# RS422.net
KiCad netlist of a schematic drawn in Altium Designer
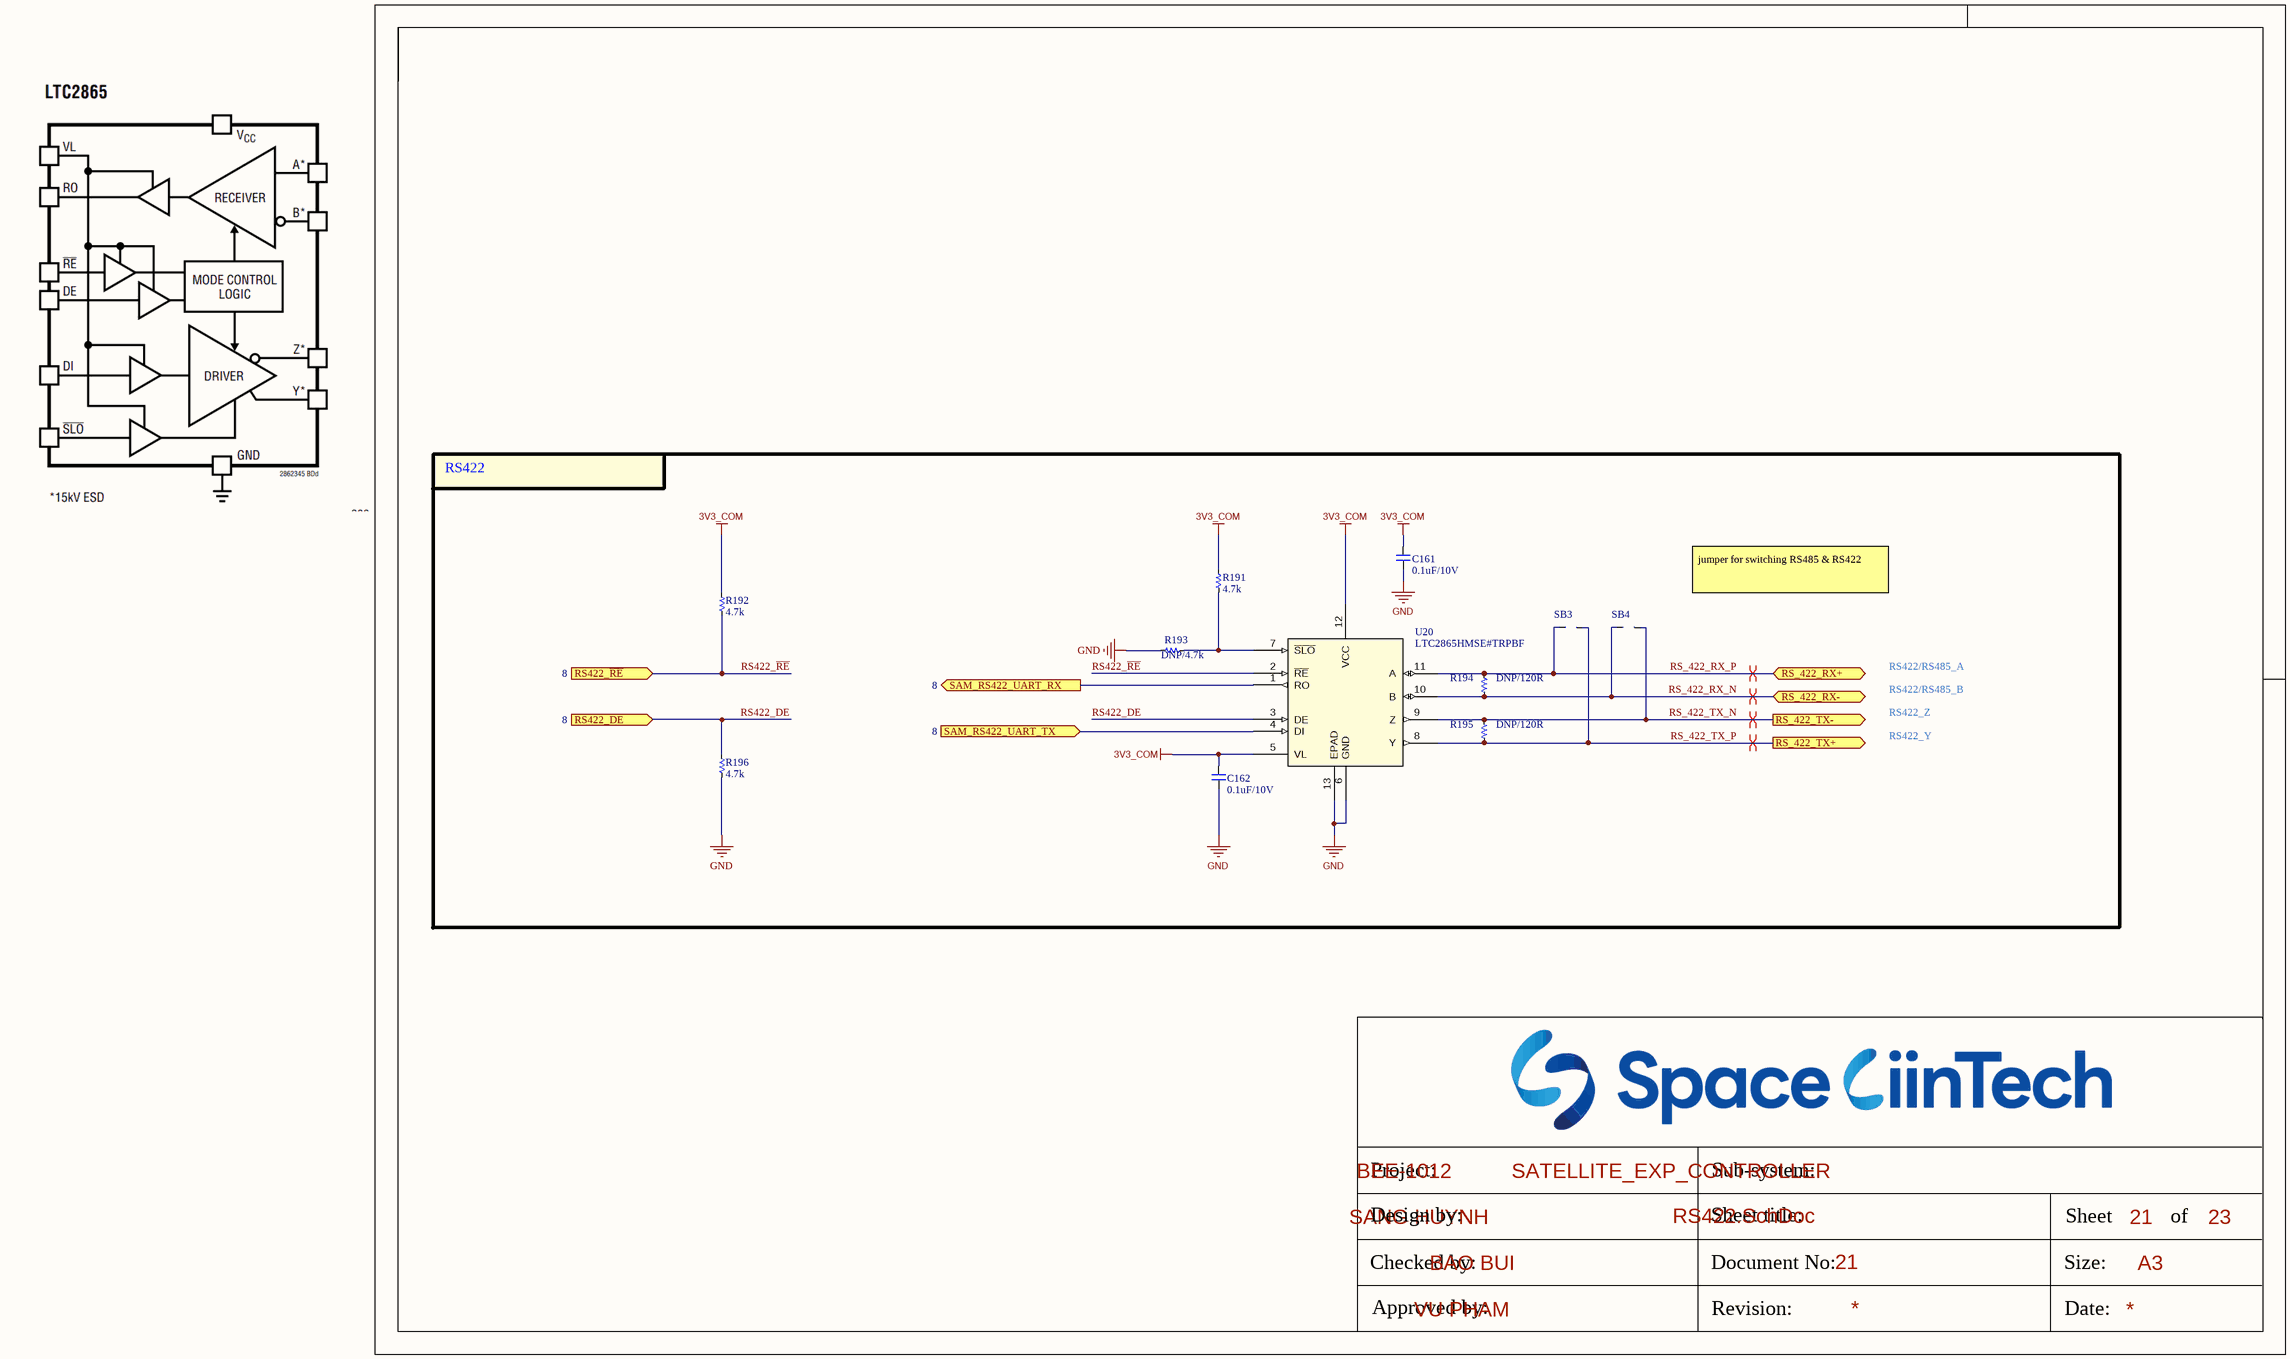
[diagram p0: RS422.SchDoc]

(export (version "E")
  (design (tool "Eeschema 10.0.6"))
  (components
    (comp (ref "C161")
      (value "0.1uF/10V")
      (footprint "CAP_C_1005X50_L")
      (description "CAP CHIP")
      (libsource (lib "IFBschelib") (part "_CAP_C_2"))
    )
    (comp (ref "C162")
      (value "0.1uF/10V")
      (footprint "CAP_C_1005X50_L")
      (description "CAP CHIP")
      (libsource (lib "IFBschelib") (part "_CAP_C_2"))
    )
    (comp (ref "R191")
      (value "4.7k")
      (footprint "RES_C_1005x30_L")
      (description "RES")
      (libsource (lib "IFBschelib") (part "_RES_B_2"))
    )
    (comp (ref "R192")
      (value "4.7k")
      (footprint "RES_C_1005x30_L")
      (description "RES")
      (libsource (lib "IFBschelib") (part "_RES_B_2"))
    )
    (comp (ref "R193")
      (value "DNP/4.7k")
      (footprint "RES_C_1005x30_L")
      (description "RES")
      (libsource (lib "IFBschelib") (part "_RES_B_2"))
    )
    (comp (ref "R194")
      (value "DNP/120R")
      (footprint "RES_C_1005x30_L")
      (description "RES")
      (libsource (lib "IFBschelib") (part "_RES_B_2"))
    )
    (comp (ref "R195")
      (value "DNP/120R")
      (footprint "RES_C_1005x30_L")
      (description "RES")
      (libsource (lib "IFBschelib") (part "_RES_B_2"))
    )
    (comp (ref "R196")
      (value "4.7k")
      (footprint "RES_C_1005x30_L")
      (description "RES")
      (libsource (lib "IFBschelib") (part "_RES_B_2"))
    )
    (comp (ref "SB3")
      (value "JUMPER")
      (footprint "JUMPER_1608")
      (libsource (lib "IFBschelib") (part "JUMPER"))
    )
    (comp (ref "SB4")
      (value "JUMPER")
      (footprint "JUMPER_1608")
      (libsource (lib "IFBschelib") (part "JUMPER"))
    )
    (comp (ref "U20")
      (value "LTC2865HMSE#TRPBF")
      (footprint "MSOP-12_MSE_LIT")
      (description "Â±60V Fault Protected 3V to 5.5V RS485/RS422 Transceivers")
      (fields (field (name "COPYRIGHT") "Copyright (C) 2025 Ultra Librarian. All rights reserved."))
      (libsource (lib "IFBschelib") (part "LTC2865HMSETRPBF"))
    )
  )
  (nets
    (net (code "1") (name "/RS422_DE") (class "Default")
      (node (ref "R196") (pin "2") (pinfunction "2_2") (pintype "passive"))
      (node (ref "U20") (pin "3") (pinfunction "DE_3") (pintype "input"))
    )
    (net (code "2") (name "/RS422_~{RE}") (class "Default")
      (node (ref "R192") (pin "1") (pinfunction "1_1") (pintype "passive"))
      (node (ref "U20") (pin "2") (pinfunction "~{RE}_2") (pintype "input"))
    )
    (net (code "3") (name "/RS_422_RX_N") (class "Default")
      (node (ref "R194") (pin "2") (pinfunction "2_2") (pintype "passive"))
      (node (ref "SB4") (pin "1") (pinfunction "1_1") (pintype "passive"))
      (node (ref "U20") (pin "10") (pinfunction "B_10") (pintype "bidirectional"))
    )
    (net (code "4") (name "/RS_422_RX_P") (class "Default")
      (node (ref "R194") (pin "1") (pinfunction "1_1") (pintype "passive"))
      (node (ref "SB3") (pin "1") (pinfunction "1_1") (pintype "passive"))
      (node (ref "U20") (pin "11") (pinfunction "A_11") (pintype "bidirectional"))
    )
    (net (code "5") (name "/RS_422_TX_N") (class "Default")
      (node (ref "R195") (pin "1") (pinfunction "1_1") (pintype "passive"))
      (node (ref "SB4") (pin "2") (pinfunction "2_2") (pintype "passive"))
      (node (ref "U20") (pin "9") (pinfunction "Z_9") (pintype "output"))
    )
    (net (code "6") (name "/RS_422_TX_P") (class "Default")
      (node (ref "R195") (pin "2") (pinfunction "2_2") (pintype "passive"))
      (node (ref "SB3") (pin "2") (pinfunction "2_2") (pintype "passive"))
      (node (ref "U20") (pin "8") (pinfunction "Y_8") (pintype "output"))
    )
    (net (code "7") (name "/SAM_RS422_UART_RX") (class "Default")
      (node (ref "U20") (pin "1") (pinfunction "RO_1") (pintype "output"))
    )
    (net (code "8") (name "/SAM_RS422_UART_TX") (class "Default")
      (node (ref "U20") (pin "4") (pinfunction "DI_4") (pintype "input"))
    )
    (net (code "9") (name "3V3_COM") (class "Default")
      (node (ref "C161") (pin "2") (pinfunction "2_2") (pintype "passive"))
      (node (ref "C162") (pin "2") (pinfunction "2_2") (pintype "passive"))
      (node (ref "R191") (pin "2") (pinfunction "2_2") (pintype "passive"))
      (node (ref "R192") (pin "2") (pinfunction "2_2") (pintype "passive"))
      (node (ref "U20") (pin "12") (pinfunction "VCC_12") (pintype "power_in"))
      (node (ref "U20") (pin "5") (pinfunction "VL_5") (pintype "power_in"))
    )
    (net (code "10") (name "GND") (class "Default")
      (node (ref "C161") (pin "1") (pinfunction "1_1") (pintype "passive"))
      (node (ref "C162") (pin "1") (pinfunction "1_1") (pintype "passive"))
      (node (ref "R193") (pin "2") (pinfunction "2_2") (pintype "passive"))
      (node (ref "R196") (pin "1") (pinfunction "1_1") (pintype "passive"))
      (node (ref "U20") (pin "13") (pinfunction "EPAD_13") (pintype "passive"))
      (node (ref "U20") (pin "6") (pinfunction "GND_6") (pintype "power_in"))
    )
    (net (code "11") (name "Net-(U20-~{SLO})") (class "Default")
      (node (ref "R191") (pin "1") (pinfunction "1_1") (pintype "passive"))
      (node (ref "R193") (pin "1") (pinfunction "1_1") (pintype "passive"))
      (node (ref "U20") (pin "7") (pinfunction "~{SLO}_7") (pintype "input"))
    )
  )
)
